# FDTI_LED_Monitor.net
KiCad netlist of a schematic drawn in Altium Designer
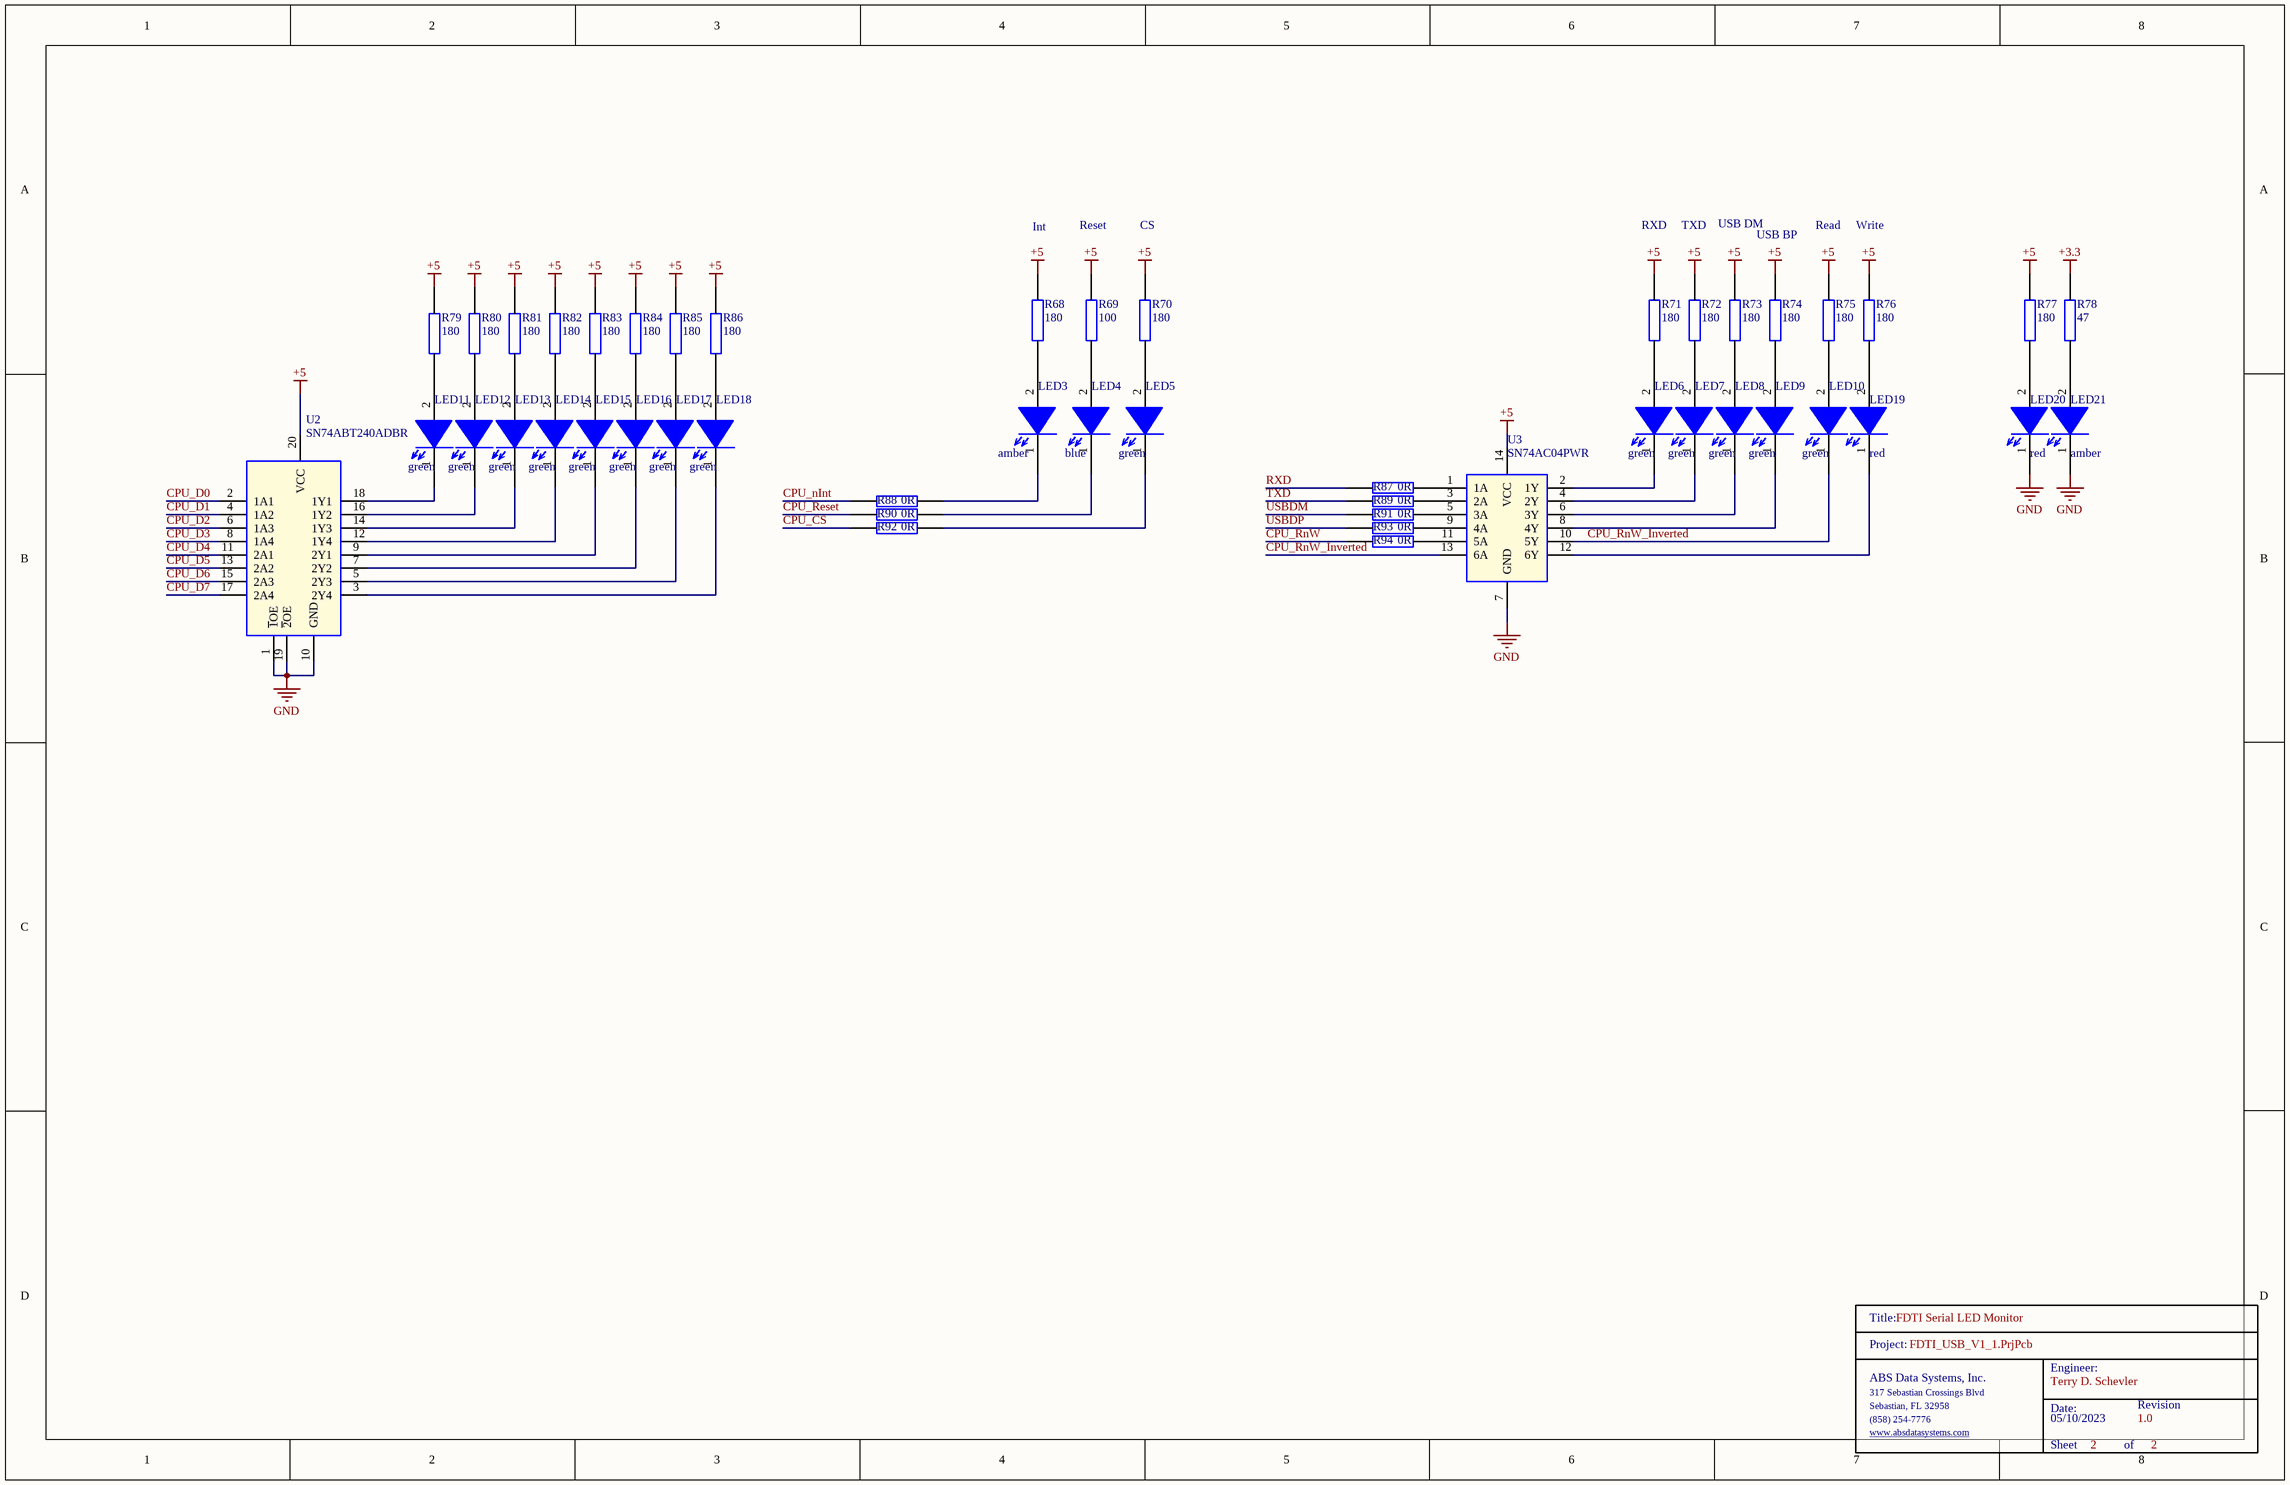
[diagram p0: FDTI_LED_Monitor.SchDoc]

(export (version "E")
  (design (tool "Eeschema 10.0.6"))
  (components
    (comp (ref "LED3")
      (value "amber")
      (footprint "0603_Diode")
      (description "Wurth Elektronik 0603 amber")
      (fields
        (field (name "MANUFACTURER") "Wurth Electronics")
        (field (name "MANUFACTURER PART NUMBER") "150060GS75000")
      )
      (libsource (lib "Misc") (part "150060AS75000"))
    )
    (comp (ref "LED4")
      (value "blue")
      (footprint "0603_Diode")
      (description "Wurth Elektronik 0603 blue")
      (fields
        (field (name "MANUFACTURER") "Wurth Electronics")
        (field (name "MANUFACTURER PART NUMBER") "150060GS75000")
      )
      (libsource (lib "Misc") (part "150060BS75000"))
    )
    (comp (ref "LED5")
      (value "green")
      (footprint "0603_Diode")
      (description "Wurth Elektronik 0603 green")
      (fields
        (field (name "MANUFACTURER") "Wurth Electronics")
        (field (name "MANUFACTURER PART NUMBER") "150060GS75000")
      )
      (libsource (lib "Misc") (part "150060GS75000"))
    )
    (comp (ref "LED6")
      (value "green")
      (footprint "0603_Diode")
      (description "Wurth Elektronik 0603 green")
      (fields
        (field (name "MANUFACTURER") "Wurth Electronics")
        (field (name "MANUFACTURER PART NUMBER") "150060GS75000")
      )
      (libsource (lib "Misc") (part "150060GS75000"))
    )
    (comp (ref "LED7")
      (value "green")
      (footprint "0603_Diode")
      (description "Wurth Elektronik 0603 green")
      (fields
        (field (name "MANUFACTURER") "Wurth Electronics")
        (field (name "MANUFACTURER PART NUMBER") "150060GS75000")
      )
      (libsource (lib "Misc") (part "150060GS75000"))
    )
    (comp (ref "LED8")
      (value "green")
      (footprint "0603_Diode")
      (description "Wurth Elektronik 0603 green")
      (fields
        (field (name "MANUFACTURER") "Wurth Electronics")
        (field (name "MANUFACTURER PART NUMBER") "150060GS75000")
      )
      (libsource (lib "Misc") (part "150060GS75000"))
    )
    (comp (ref "LED9")
      (value "green")
      (footprint "0603_Diode")
      (description "Wurth Elektronik 0603 green")
      (fields
        (field (name "MANUFACTURER") "Wurth Electronics")
        (field (name "MANUFACTURER PART NUMBER") "150060GS75000")
      )
      (libsource (lib "Misc") (part "150060GS75000"))
    )
    (comp (ref "LED10")
      (value "green")
      (footprint "0603_Diode")
      (description "Wurth Elektronik 0603 green")
      (fields
        (field (name "MANUFACTURER") "Wurth Electronics")
        (field (name "MANUFACTURER PART NUMBER") "150060GS75000")
      )
      (libsource (lib "Misc") (part "150060GS75000"))
    )
    (comp (ref "LED11")
      (value "green")
      (footprint "0603_Diode")
      (description "Wurth Elektronik 0603 green")
      (fields
        (field (name "MANUFACTURER") "Wurth Electronics")
        (field (name "MANUFACTURER PART NUMBER") "150060GS75000")
      )
      (libsource (lib "Misc") (part "150060GS75000"))
    )
    (comp (ref "LED12")
      (value "green")
      (footprint "0603_Diode")
      (description "Wurth Elektronik 0603 green")
      (fields
        (field (name "MANUFACTURER") "Wurth Electronics")
        (field (name "MANUFACTURER PART NUMBER") "150060GS75000")
      )
      (libsource (lib "Misc") (part "150060GS75000"))
    )
    (comp (ref "LED13")
      (value "green")
      (footprint "0603_Diode")
      (description "Wurth Elektronik 0603 green")
      (fields
        (field (name "MANUFACTURER") "Wurth Electronics")
        (field (name "MANUFACTURER PART NUMBER") "150060GS75000")
      )
      (libsource (lib "Misc") (part "150060GS75000"))
    )
    (comp (ref "LED14")
      (value "green")
      (footprint "0603_Diode")
      (description "Wurth Elektronik 0603 green")
      (fields
        (field (name "MANUFACTURER") "Wurth Electronics")
        (field (name "MANUFACTURER PART NUMBER") "150060GS75000")
      )
      (libsource (lib "Misc") (part "150060GS75000"))
    )
    (comp (ref "LED15")
      (value "green")
      (footprint "0603_Diode")
      (description "Wurth Elektronik 0603 green")
      (fields
        (field (name "MANUFACTURER") "Wurth Electronics")
        (field (name "MANUFACTURER PART NUMBER") "150060GS75000")
      )
      (libsource (lib "Misc") (part "150060GS75000"))
    )
    (comp (ref "LED16")
      (value "green")
      (footprint "0603_Diode")
      (description "Wurth Elektronik 0603 green")
      (fields
        (field (name "MANUFACTURER") "Wurth Electronics")
        (field (name "MANUFACTURER PART NUMBER") "150060GS75000")
      )
      (libsource (lib "Misc") (part "150060GS75000"))
    )
    (comp (ref "LED17")
      (value "green")
      (footprint "0603_Diode")
      (description "Wurth Elektronik 0603 green")
      (fields
        (field (name "MANUFACTURER") "Wurth Electronics")
        (field (name "MANUFACTURER PART NUMBER") "150060GS75000")
      )
      (libsource (lib "Misc") (part "150060GS75000"))
    )
    (comp (ref "LED18")
      (value "green")
      (footprint "0603_Diode")
      (description "Wurth Elektronik 0603 green")
      (fields
        (field (name "MANUFACTURER") "Wurth Electronics")
        (field (name "MANUFACTURER PART NUMBER") "150060GS75000")
      )
      (libsource (lib "Misc") (part "150060GS75000"))
    )
    (comp (ref "LED19")
      (value "red")
      (footprint "0603_Diode")
      (description "Wurth Elektronik 0603 red")
      (fields
        (field (name "MANUFACTURER") "Wurth Electronics")
        (field (name "MANUFACTURER PART NUMBER") "150060GS75000")
      )
      (libsource (lib "Misc") (part "150060RS75000"))
    )
    (comp (ref "LED20")
      (value "red")
      (footprint "0603_Diode")
      (description "Wurth Elektronik 0603 red")
      (fields
        (field (name "MANUFACTURER") "Wurth Electronics")
        (field (name "MANUFACTURER PART NUMBER") "150060GS75000")
      )
      (libsource (lib "Misc") (part "150060RS75000"))
    )
    (comp (ref "LED21")
      (value "amber")
      (footprint "0603_Diode")
      (description "Wurth Elektronik 0603 amber")
      (fields
        (field (name "MANUFACTURER") "Wurth Electronics")
        (field (name "MANUFACTURER PART NUMBER") "150060GS75000")
      )
      (libsource (lib "Misc") (part "150060AS75000"))
    )
    (comp (ref "R68")
      (value "180")
      (footprint "0603")
      (description "YAGEO 0603 180 ohm")
      (fields
        (field (name "MOUSER PART NUMBER") "603-RC0603JR-070RL")
        (field (name "MANUFACTURER_PART_NUMBER") "RC0603JR-070RL")
      )
      (libsource (lib "Resistors") (part "RC0603FR-13180RL"))
    )
    (comp (ref "R69")
      (value "100")
      (footprint "0603")
      (description "YAGEO 0603 100 ohm")
      (fields
        (field (name "MOUSER PART NUMBER") "603-RC0603JR-070RL")
        (field (name "MANUFACTURER_PART_NUMBER") "RC0603JR-070RL")
      )
      (libsource (lib "Resistors") (part "RC0603FR-10100RL"))
    )
    (comp (ref "R70")
      (value "180")
      (footprint "0603")
      (description "YAGEO 0603 180 ohm")
      (fields
        (field (name "MOUSER PART NUMBER") "603-RC0603JR-070RL")
        (field (name "MANUFACTURER_PART_NUMBER") "RC0603JR-070RL")
      )
      (libsource (lib "Resistors") (part "RC0603FR-13180RL"))
    )
    (comp (ref "R71")
      (value "180")
      (footprint "0603")
      (description "YAGEO 0603 180 ohm")
      (fields
        (field (name "MOUSER PART NUMBER") "603-RC0603JR-070RL")
        (field (name "MANUFACTURER_PART_NUMBER") "RC0603JR-070RL")
      )
      (libsource (lib "Resistors") (part "RC0603FR-13180RL"))
    )
    (comp (ref "R72")
      (value "180")
      (footprint "0603")
      (description "YAGEO 0603 180 ohm")
      (fields
        (field (name "MOUSER PART NUMBER") "603-RC0603JR-070RL")
        (field (name "MANUFACTURER_PART_NUMBER") "RC0603JR-070RL")
      )
      (libsource (lib "Resistors") (part "RC0603FR-13180RL"))
    )
    (comp (ref "R73")
      (value "180")
      (footprint "0603")
      (description "YAGEO 0603 180 ohm")
      (fields
        (field (name "MOUSER PART NUMBER") "603-RC0603JR-070RL")
        (field (name "MANUFACTURER_PART_NUMBER") "RC0603JR-070RL")
      )
      (libsource (lib "Resistors") (part "RC0603FR-13180RL"))
    )
    (comp (ref "R74")
      (value "180")
      (footprint "0603")
      (description "YAGEO 0603 180 ohm")
      (fields
        (field (name "MOUSER PART NUMBER") "603-RC0603JR-070RL")
        (field (name "MANUFACTURER_PART_NUMBER") "RC0603JR-070RL")
      )
      (libsource (lib "Resistors") (part "RC0603FR-13180RL"))
    )
    (comp (ref "R75")
      (value "180")
      (footprint "0603")
      (description "YAGEO 0603 180 ohm")
      (fields
        (field (name "MOUSER PART NUMBER") "603-RC0603JR-070RL")
        (field (name "MANUFACTURER_PART_NUMBER") "RC0603JR-070RL")
      )
      (libsource (lib "Resistors") (part "RC0603FR-13180RL"))
    )
    (comp (ref "R76")
      (value "180")
      (footprint "0603")
      (description "YAGEO 0603 180 ohm")
      (fields
        (field (name "MOUSER PART NUMBER") "603-RC0603JR-070RL")
        (field (name "MANUFACTURER_PART_NUMBER") "RC0603JR-070RL")
      )
      (libsource (lib "Resistors") (part "RC0603FR-13180RL"))
    )
    (comp (ref "R77")
      (value "180")
      (footprint "0603")
      (description "YAGEO 0603 180 ohm")
      (fields
        (field (name "MOUSER PART NUMBER") "603-RC0603JR-070RL")
        (field (name "MANUFACTURER_PART_NUMBER") "RC0603JR-070RL")
      )
      (libsource (lib "Resistors") (part "RC0603FR-13180RL"))
    )
    (comp (ref "R78")
      (value "47")
      (footprint "0603")
      (description "YAGEO 0603 47")
      (fields
        (field (name "MOUSER PART NUMBER") "603-RC0603JR-070RL")
        (field (name "MANUFACTURER_PART_NUMBER") "RC0603JR-070RL")
      )
      (libsource (lib "Resistors") (part "RC0603FR-0747KL"))
    )
    (comp (ref "R79")
      (value "180")
      (footprint "0603")
      (description "YAGEO 0603 180 ohm")
      (fields
        (field (name "MOUSER PART NUMBER") "603-RC0603JR-070RL")
        (field (name "MANUFACTURER_PART_NUMBER") "RC0603JR-070RL")
      )
      (libsource (lib "Resistors") (part "RC0603FR-13180RL"))
    )
    (comp (ref "R80")
      (value "180")
      (footprint "0603")
      (description "YAGEO 0603 180 ohm")
      (fields
        (field (name "MOUSER PART NUMBER") "603-RC0603JR-070RL")
        (field (name "MANUFACTURER_PART_NUMBER") "RC0603JR-070RL")
      )
      (libsource (lib "Resistors") (part "RC0603FR-13180RL"))
    )
    (comp (ref "R81")
      (value "180")
      (footprint "0603")
      (description "YAGEO 0603 180 ohm")
      (fields
        (field (name "MOUSER PART NUMBER") "603-RC0603JR-070RL")
        (field (name "MANUFACTURER_PART_NUMBER") "RC0603JR-070RL")
      )
      (libsource (lib "Resistors") (part "RC0603FR-13180RL"))
    )
    (comp (ref "R82")
      (value "180")
      (footprint "0603")
      (description "YAGEO 0603 180 ohm")
      (fields
        (field (name "MOUSER PART NUMBER") "603-RC0603JR-070RL")
        (field (name "MANUFACTURER_PART_NUMBER") "RC0603JR-070RL")
      )
      (libsource (lib "Resistors") (part "RC0603FR-13180RL"))
    )
    (comp (ref "R83")
      (value "180")
      (footprint "0603")
      (description "YAGEO 0603 180 ohm")
      (fields
        (field (name "MOUSER PART NUMBER") "603-RC0603JR-070RL")
        (field (name "MANUFACTURER_PART_NUMBER") "RC0603JR-070RL")
      )
      (libsource (lib "Resistors") (part "RC0603FR-13180RL"))
    )
    (comp (ref "R84")
      (value "180")
      (footprint "0603")
      (description "YAGEO 0603 180 ohm")
      (fields
        (field (name "MOUSER PART NUMBER") "603-RC0603JR-070RL")
        (field (name "MANUFACTURER_PART_NUMBER") "RC0603JR-070RL")
      )
      (libsource (lib "Resistors") (part "RC0603FR-13180RL"))
    )
    (comp (ref "R85")
      (value "180")
      (footprint "0603")
      (description "YAGEO 0603 180 ohm")
      (fields
        (field (name "MOUSER PART NUMBER") "603-RC0603JR-070RL")
        (field (name "MANUFACTURER_PART_NUMBER") "RC0603JR-070RL")
      )
      (libsource (lib "Resistors") (part "RC0603FR-13180RL"))
    )
    (comp (ref "R86")
      (value "180")
      (footprint "0603")
      (description "YAGEO 0603 180 ohm")
      (fields
        (field (name "MOUSER PART NUMBER") "603-RC0603JR-070RL")
        (field (name "MANUFACTURER_PART_NUMBER") "RC0603JR-070RL")
      )
      (libsource (lib "Resistors") (part "RC0603FR-13180RL"))
    )
    (comp (ref "R87")
      (value "0R")
      (footprint "0603")
      (description "YAGEO 0603 0 ohm")
      (fields
        (field (name "MOUSER PART NUMBER") "603-RC0603JR-070RL")
        (field (name "MANUFACTURER_PART_NUMBER") "RC0603JR-070RL")
      )
      (libsource (lib "Resistors") (part "RC0603JR-070RL"))
    )
    (comp (ref "R88")
      (value "0R")
      (footprint "0603")
      (description "YAGEO 0603 0 ohm")
      (fields
        (field (name "MOUSER PART NUMBER") "603-RC0603JR-070RL")
        (field (name "MANUFACTURER_PART_NUMBER") "RC0603JR-070RL")
      )
      (libsource (lib "Resistors") (part "RC0603JR-070RL"))
    )
    (comp (ref "R89")
      (value "0R")
      (footprint "0603")
      (description "YAGEO 0603 0 ohm")
      (fields
        (field (name "MOUSER PART NUMBER") "603-RC0603JR-070RL")
        (field (name "MANUFACTURER_PART_NUMBER") "RC0603JR-070RL")
      )
      (libsource (lib "Resistors") (part "RC0603JR-070RL"))
    )
    (comp (ref "R90")
      (value "0R")
      (footprint "0603")
      (description "YAGEO 0603 0 ohm")
      (fields
        (field (name "MOUSER PART NUMBER") "603-RC0603JR-070RL")
        (field (name "MANUFACTURER_PART_NUMBER") "RC0603JR-070RL")
      )
      (libsource (lib "Resistors") (part "RC0603JR-070RL"))
    )
    (comp (ref "R91")
      (value "0R")
      (footprint "0603")
      (description "YAGEO 0603 0 ohm")
      (fields
        (field (name "MOUSER PART NUMBER") "603-RC0603JR-070RL")
        (field (name "MANUFACTURER_PART_NUMBER") "RC0603JR-070RL")
      )
      (libsource (lib "Resistors") (part "RC0603JR-070RL"))
    )
    (comp (ref "R92")
      (value "0R")
      (footprint "0603")
      (description "YAGEO 0603 0 ohm")
      (fields
        (field (name "MOUSER PART NUMBER") "603-RC0603JR-070RL")
        (field (name "MANUFACTURER_PART_NUMBER") "RC0603JR-070RL")
      )
      (libsource (lib "Resistors") (part "RC0603JR-070RL"))
    )
    (comp (ref "R93")
      (value "0R")
      (footprint "0603")
      (description "YAGEO 0603 0 ohm")
      (fields
        (field (name "MOUSER PART NUMBER") "603-RC0603JR-070RL")
        (field (name "MANUFACTURER_PART_NUMBER") "RC0603JR-070RL")
      )
      (libsource (lib "Resistors") (part "RC0603JR-070RL"))
    )
    (comp (ref "R94")
      (value "0R")
      (footprint "0603")
      (description "YAGEO 0603 0 ohm")
      (fields
        (field (name "MOUSER PART NUMBER") "603-RC0603JR-070RL")
        (field (name "MANUFACTURER_PART_NUMBER") "RC0603JR-070RL")
      )
      (libsource (lib "Resistors") (part "RC0603JR-070RL"))
    )
    (comp (ref "TitleBlock_2") (value "TitleBlock") (libsource (lib "Misc") (part "TitleBlock")))
    (comp (ref "U2")
      (value "SN74ABT240ADBR")
      (footprint "SOP65P780X200-20N")
      (description "Octal Buffers/Drivers With 3-State Outputs")
      (fields (field (name "MOUSER PART NUMBER") "595-SN74ABT240ADBR"))
      (libsource (lib "Logic") (part "SN74ABT240ADBR"))
    )
    (comp (ref "U3")
      (value "SN74AC04PWR")
      (footprint "SOP65P640X120-14N")
      (description "Hex Inverters")
      (fields (field (name "MOUSER PART NUMBER") "595-SN74AC04PWR"))
      (libsource (lib "Logic") (part "SN74AC04PWR"))
    )
  )
  (nets
    (net (code "1") (name "+3.3") (class "Default")
      (node (ref "R78") (pin "1") (pinfunction "1_1") (pintype "passive"))
    )
    (net (code "2") (name "+5") (class "Default")
      (node (ref "R68") (pin "2") (pinfunction "2_2") (pintype "passive"))
      (node (ref "R69") (pin "1") (pinfunction "1_1") (pintype "passive"))
      (node (ref "R70") (pin "2") (pinfunction "2_2") (pintype "passive"))
      (node (ref "R71") (pin "2") (pinfunction "2_2") (pintype "passive"))
      (node (ref "R72") (pin "2") (pinfunction "2_2") (pintype "passive"))
      (node (ref "R73") (pin "2") (pinfunction "2_2") (pintype "passive"))
      (node (ref "R74") (pin "2") (pinfunction "2_2") (pintype "passive"))
      (node (ref "R75") (pin "2") (pinfunction "2_2") (pintype "passive"))
      (node (ref "R76") (pin "2") (pinfunction "2_2") (pintype "passive"))
      (node (ref "R77") (pin "2") (pinfunction "2_2") (pintype "passive"))
      (node (ref "R79") (pin "2") (pinfunction "2_2") (pintype "passive"))
      (node (ref "R80") (pin "2") (pinfunction "2_2") (pintype "passive"))
      (node (ref "R81") (pin "2") (pinfunction "2_2") (pintype "passive"))
      (node (ref "R82") (pin "2") (pinfunction "2_2") (pintype "passive"))
      (node (ref "R83") (pin "2") (pinfunction "2_2") (pintype "passive"))
      (node (ref "R84") (pin "2") (pinfunction "2_2") (pintype "passive"))
      (node (ref "R85") (pin "2") (pinfunction "2_2") (pintype "passive"))
      (node (ref "R86") (pin "2") (pinfunction "2_2") (pintype "passive"))
      (node (ref "U2") (pin "20") (pinfunction "VCC_20") (pintype "passive"))
      (node (ref "U3") (pin "14") (pinfunction "VCC_14") (pintype "passive"))
    )
    (net (code "3") (name "/CPU_CS") (class "Default")
      (node (ref "R92") (pin "1") (pinfunction "1_1") (pintype "passive"))
    )
    (net (code "4") (name "/CPU_D0") (class "Default")
      (node (ref "U2") (pin "2") (pinfunction "1A1_2") (pintype "passive"))
    )
    (net (code "5") (name "/CPU_D1") (class "Default")
      (node (ref "U2") (pin "4") (pinfunction "1A2_4") (pintype "passive"))
    )
    (net (code "6") (name "/CPU_D2") (class "Default")
      (node (ref "U2") (pin "6") (pinfunction "1A3_6") (pintype "passive"))
    )
    (net (code "7") (name "/CPU_D3") (class "Default")
      (node (ref "U2") (pin "8") (pinfunction "1A4_8") (pintype "passive"))
    )
    (net (code "8") (name "/CPU_D4") (class "Default")
      (node (ref "U2") (pin "11") (pinfunction "2A1_11") (pintype "passive"))
    )
    (net (code "9") (name "/CPU_D5") (class "Default")
      (node (ref "U2") (pin "13") (pinfunction "2A2_13") (pintype "passive"))
    )
    (net (code "10") (name "/CPU_D6") (class "Default")
      (node (ref "U2") (pin "15") (pinfunction "2A3_15") (pintype "passive"))
    )
    (net (code "11") (name "/CPU_D7") (class "Default")
      (node (ref "U2") (pin "17") (pinfunction "2A4_17") (pintype "passive"))
    )
    (net (code "12") (name "/CPU_Reset") (class "Default")
      (node (ref "R90") (pin "1") (pinfunction "1_1") (pintype "passive"))
    )
    (net (code "13") (name "/CPU_RnW") (class "Default")
      (node (ref "R94") (pin "1") (pinfunction "1_1") (pintype "passive"))
    )
    (net (code "14") (name "/CPU_RnW_Inverted") (class "Default")
      (node (ref "LED10") (pin "1") (pinfunction "K_1") (pintype "passive"))
      (node (ref "U3") (pin "10") (pinfunction "5Y_10") (pintype "passive"))
      (node (ref "U3") (pin "13") (pinfunction "6A_13") (pintype "passive"))
    )
    (net (code "15") (name "/CPU_nInt") (class "Default")
      (node (ref "R88") (pin "1") (pinfunction "1_1") (pintype "passive"))
    )
    (net (code "16") (name "/RXD") (class "Default")
      (node (ref "R87") (pin "1") (pinfunction "1_1") (pintype "passive"))
    )
    (net (code "17") (name "/TXD") (class "Default")
      (node (ref "R89") (pin "1") (pinfunction "1_1") (pintype "passive"))
    )
    (net (code "18") (name "/USBDM") (class "Default")
      (node (ref "R91") (pin "1") (pinfunction "1_1") (pintype "passive"))
    )
    (net (code "19") (name "/USBDP") (class "Default")
      (node (ref "R93") (pin "1") (pinfunction "1_1") (pintype "passive"))
    )
    (net (code "20") (name "GND") (class "Default")
      (node (ref "LED20") (pin "1") (pinfunction "K_1") (pintype "passive"))
      (node (ref "LED21") (pin "1") (pinfunction "K_1") (pintype "passive"))
      (node (ref "U2") (pin "1") (pinfunction "~{1}OE_1") (pintype "passive"))
      (node (ref "U2") (pin "10") (pinfunction "GND_10") (pintype "passive"))
      (node (ref "U2") (pin "19") (pinfunction "~{2}OE_19") (pintype "passive"))
      (node (ref "U3") (pin "7") (pinfunction "GND_7") (pintype "passive"))
    )
    (net (code "21") (name "Net-(LED3-A)") (class "Default")
      (node (ref "LED3") (pin "2") (pinfunction "A_2") (pintype "passive"))
      (node (ref "R68") (pin "1") (pinfunction "1_1") (pintype "passive"))
    )
    (net (code "22") (name "Net-(LED3-K)") (class "Default")
      (node (ref "LED3") (pin "1") (pinfunction "K_1") (pintype "passive"))
      (node (ref "R88") (pin "2") (pinfunction "2_2") (pintype "passive"))
    )
    (net (code "23") (name "Net-(LED4-A)") (class "Default")
      (node (ref "LED4") (pin "2") (pinfunction "A_2") (pintype "passive"))
      (node (ref "R69") (pin "2") (pinfunction "2_2") (pintype "passive"))
    )
    (net (code "24") (name "Net-(LED4-K)") (class "Default")
      (node (ref "LED4") (pin "1") (pinfunction "K_1") (pintype "passive"))
      (node (ref "R90") (pin "2") (pinfunction "2_2") (pintype "passive"))
    )
    (net (code "25") (name "Net-(LED5-A)") (class "Default")
      (node (ref "LED5") (pin "2") (pinfunction "A_2") (pintype "passive"))
      (node (ref "R70") (pin "1") (pinfunction "1_1") (pintype "passive"))
    )
    (net (code "26") (name "Net-(LED5-K)") (class "Default")
      (node (ref "LED5") (pin "1") (pinfunction "K_1") (pintype "passive"))
      (node (ref "R92") (pin "2") (pinfunction "2_2") (pintype "passive"))
    )
    (net (code "27") (name "Net-(LED6-A)") (class "Default")
      (node (ref "LED6") (pin "2") (pinfunction "A_2") (pintype "passive"))
      (node (ref "R71") (pin "1") (pinfunction "1_1") (pintype "passive"))
    )
    (net (code "28") (name "Net-(LED6-K)") (class "Default")
      (node (ref "LED6") (pin "1") (pinfunction "K_1") (pintype "passive"))
      (node (ref "U3") (pin "2") (pinfunction "1Y_2") (pintype "passive"))
    )
    (net (code "29") (name "Net-(LED7-A)") (class "Default")
      (node (ref "LED7") (pin "2") (pinfunction "A_2") (pintype "passive"))
      (node (ref "R72") (pin "1") (pinfunction "1_1") (pintype "passive"))
    )
    (net (code "30") (name "Net-(LED7-K)") (class "Default")
      (node (ref "LED7") (pin "1") (pinfunction "K_1") (pintype "passive"))
      (node (ref "U3") (pin "4") (pinfunction "2Y_4") (pintype "passive"))
    )
    (net (code "31") (name "Net-(LED8-A)") (class "Default")
      (node (ref "LED8") (pin "2") (pinfunction "A_2") (pintype "passive"))
      (node (ref "R73") (pin "1") (pinfunction "1_1") (pintype "passive"))
    )
    (net (code "32") (name "Net-(LED8-K)") (class "Default")
      (node (ref "LED8") (pin "1") (pinfunction "K_1") (pintype "passive"))
      (node (ref "U3") (pin "6") (pinfunction "3Y_6") (pintype "passive"))
    )
    (net (code "33") (name "Net-(LED9-A)") (class "Default")
      (node (ref "LED9") (pin "2") (pinfunction "A_2") (pintype "passive"))
      (node (ref "R74") (pin "1") (pinfunction "1_1") (pintype "passive"))
    )
    (net (code "34") (name "Net-(LED9-K)") (class "Default")
      (node (ref "LED9") (pin "1") (pinfunction "K_1") (pintype "passive"))
      (node (ref "U3") (pin "8") (pinfunction "4Y_8") (pintype "passive"))
    )
    (net (code "35") (name "Net-(LED10-A)") (class "Default")
      (node (ref "LED10") (pin "2") (pinfunction "A_2") (pintype "passive"))
      (node (ref "R75") (pin "1") (pinfunction "1_1") (pintype "passive"))
    )
    (net (code "36") (name "Net-(LED11-A)") (class "Default")
      (node (ref "LED11") (pin "2") (pinfunction "A_2") (pintype "passive"))
      (node (ref "R79") (pin "1") (pinfunction "1_1") (pintype "passive"))
    )
    (net (code "37") (name "Net-(LED11-K)") (class "Default")
      (node (ref "LED11") (pin "1") (pinfunction "K_1") (pintype "passive"))
      (node (ref "U2") (pin "18") (pinfunction "1Y1_18") (pintype "passive"))
    )
    (net (code "38") (name "Net-(LED12-A)") (class "Default")
      (node (ref "LED12") (pin "2") (pinfunction "A_2") (pintype "passive"))
      (node (ref "R80") (pin "1") (pinfunction "1_1") (pintype "passive"))
    )
    (net (code "39") (name "Net-(LED12-K)") (class "Default")
      (node (ref "LED12") (pin "1") (pinfunction "K_1") (pintype "passive"))
      (node (ref "U2") (pin "16") (pinfunction "1Y2_16") (pintype "passive"))
    )
    (net (code "40") (name "Net-(LED13-A)") (class "Default")
      (node (ref "LED13") (pin "2") (pinfunction "A_2") (pintype "passive"))
      (node (ref "R81") (pin "1") (pinfunction "1_1") (pintype "passive"))
    )
    (net (code "41") (name "Net-(LED13-K)") (class "Default")
      (node (ref "LED13") (pin "1") (pinfunction "K_1") (pintype "passive"))
      (node (ref "U2") (pin "14") (pinfunction "1Y3_14") (pintype "passive"))
    )
    (net (code "42") (name "Net-(LED14-A)") (class "Default")
      (node (ref "LED14") (pin "2") (pinfunction "A_2") (pintype "passive"))
      (node (ref "R82") (pin "1") (pinfunction "1_1") (pintype "passive"))
    )
    (net (code "43") (name "Net-(LED14-K)") (class "Default")
      (node (ref "LED14") (pin "1") (pinfunction "K_1") (pintype "passive"))
      (node (ref "U2") (pin "12") (pinfunction "1Y4_12") (pintype "passive"))
    )
    (net (code "44") (name "Net-(LED15-A)") (class "Default")
      (node (ref "LED15") (pin "2") (pinfunction "A_2") (pintype "passive"))
      (node (ref "R83") (pin "1") (pinfunction "1_1") (pintype "passive"))
    )
    (net (code "45") (name "Net-(LED15-K)") (class "Default")
      (node (ref "LED15") (pin "1") (pinfunction "K_1") (pintype "passive"))
      (node (ref "U2") (pin "9") (pinfunction "2Y1_9") (pintype "passive"))
    )
    (net (code "46") (name "Net-(LED16-A)") (class "Default")
      (node (ref "LED16") (pin "2") (pinfunction "A_2") (pintype "passive"))
      (node (ref "R84") (pin "1") (pinfunction "1_1") (pintype "passive"))
    )
    (net (code "47") (name "Net-(LED16-K)") (class "Default")
      (node (ref "LED16") (pin "1") (pinfunction "K_1") (pintype "passive"))
      (node (ref "U2") (pin "7") (pinfunction "2Y2_7") (pintype "passive"))
    )
    (net (code "48") (name "Net-(LED17-A)") (class "Default")
      (node (ref "LED17") (pin "2") (pinfunction "A_2") (pintype "passive"))
      (node (ref "R85") (pin "1") (pinfunction "1_1") (pintype "passive"))
    )
    (net (code "49") (name "Net-(LED17-K)") (class "Default")
      (node (ref "LED17") (pin "1") (pinfunction "K_1") (pintype "passive"))
      (node (ref "U2") (pin "5") (pinfunction "2Y3_5") (pintype "passive"))
    )
    (net (code "50") (name "Net-(LED18-A)") (class "Default")
      (node (ref "LED18") (pin "2") (pinfunction "A_2") (pintype "passive"))
      (node (ref "R86") (pin "1") (pinfunction "1_1") (pintype "passive"))
    )
    (net (code "51") (name "Net-(LED18-K)") (class "Default")
      (node (ref "LED18") (pin "1") (pinfunction "K_1") (pintype "passive"))
      (node (ref "U2") (pin "3") (pinfunction "2Y4_3") (pintype "passive"))
    )
    (net (code "52") (name "Net-(LED19-A)") (class "Default")
      (node (ref "LED19") (pin "2") (pinfunction "A_2") (pintype "passive"))
      (node (ref "R76") (pin "1") (pinfunction "1_1") (pintype "passive"))
    )
    (net (code "53") (name "Net-(LED19-K)") (class "Default")
      (node (ref "LED19") (pin "1") (pinfunction "K_1") (pintype "passive"))
      (node (ref "U3") (pin "12") (pinfunction "6Y_12") (pintype "passive"))
    )
    (net (code "54") (name "Net-(LED20-A)") (class "Default")
      (node (ref "LED20") (pin "2") (pinfunction "A_2") (pintype "passive"))
      (node (ref "R77") (pin "1") (pinfunction "1_1") (pintype "passive"))
    )
    (net (code "55") (name "Net-(LED21-A)") (class "Default")
      (node (ref "LED21") (pin "2") (pinfunction "A_2") (pintype "passive"))
      (node (ref "R78") (pin "2") (pinfunction "2_2") (pintype "passive"))
    )
    (net (code "56") (name "Net-(U3-1A)") (class "Default")
      (node (ref "R87") (pin "2") (pinfunction "2_2") (pintype "passive"))
      (node (ref "U3") (pin "1") (pinfunction "1A_1") (pintype "passive"))
    )
    (net (code "57") (name "Net-(U3-2A)") (class "Default")
      (node (ref "R89") (pin "2") (pinfunction "2_2") (pintype "passive"))
      (node (ref "U3") (pin "3") (pinfunction "2A_3") (pintype "passive"))
    )
    (net (code "58") (name "Net-(U3-3A)") (class "Default")
      (node (ref "R91") (pin "2") (pinfunction "2_2") (pintype "passive"))
      (node (ref "U3") (pin "5") (pinfunction "3A_5") (pintype "passive"))
    )
    (net (code "59") (name "Net-(U3-4A)") (class "Default")
      (node (ref "R93") (pin "2") (pinfunction "2_2") (pintype "passive"))
      (node (ref "U3") (pin "9") (pinfunction "4A_9") (pintype "passive"))
    )
    (net (code "60") (name "Net-(U3-5A)") (class "Default")
      (node (ref "R94") (pin "2") (pinfunction "2_2") (pintype "passive"))
      (node (ref "U3") (pin "11") (pinfunction "5A_11") (pintype "passive"))
    )
  )
)
